# MKVCO.net
KiCad netlist of a schematic drawn in EAGLE
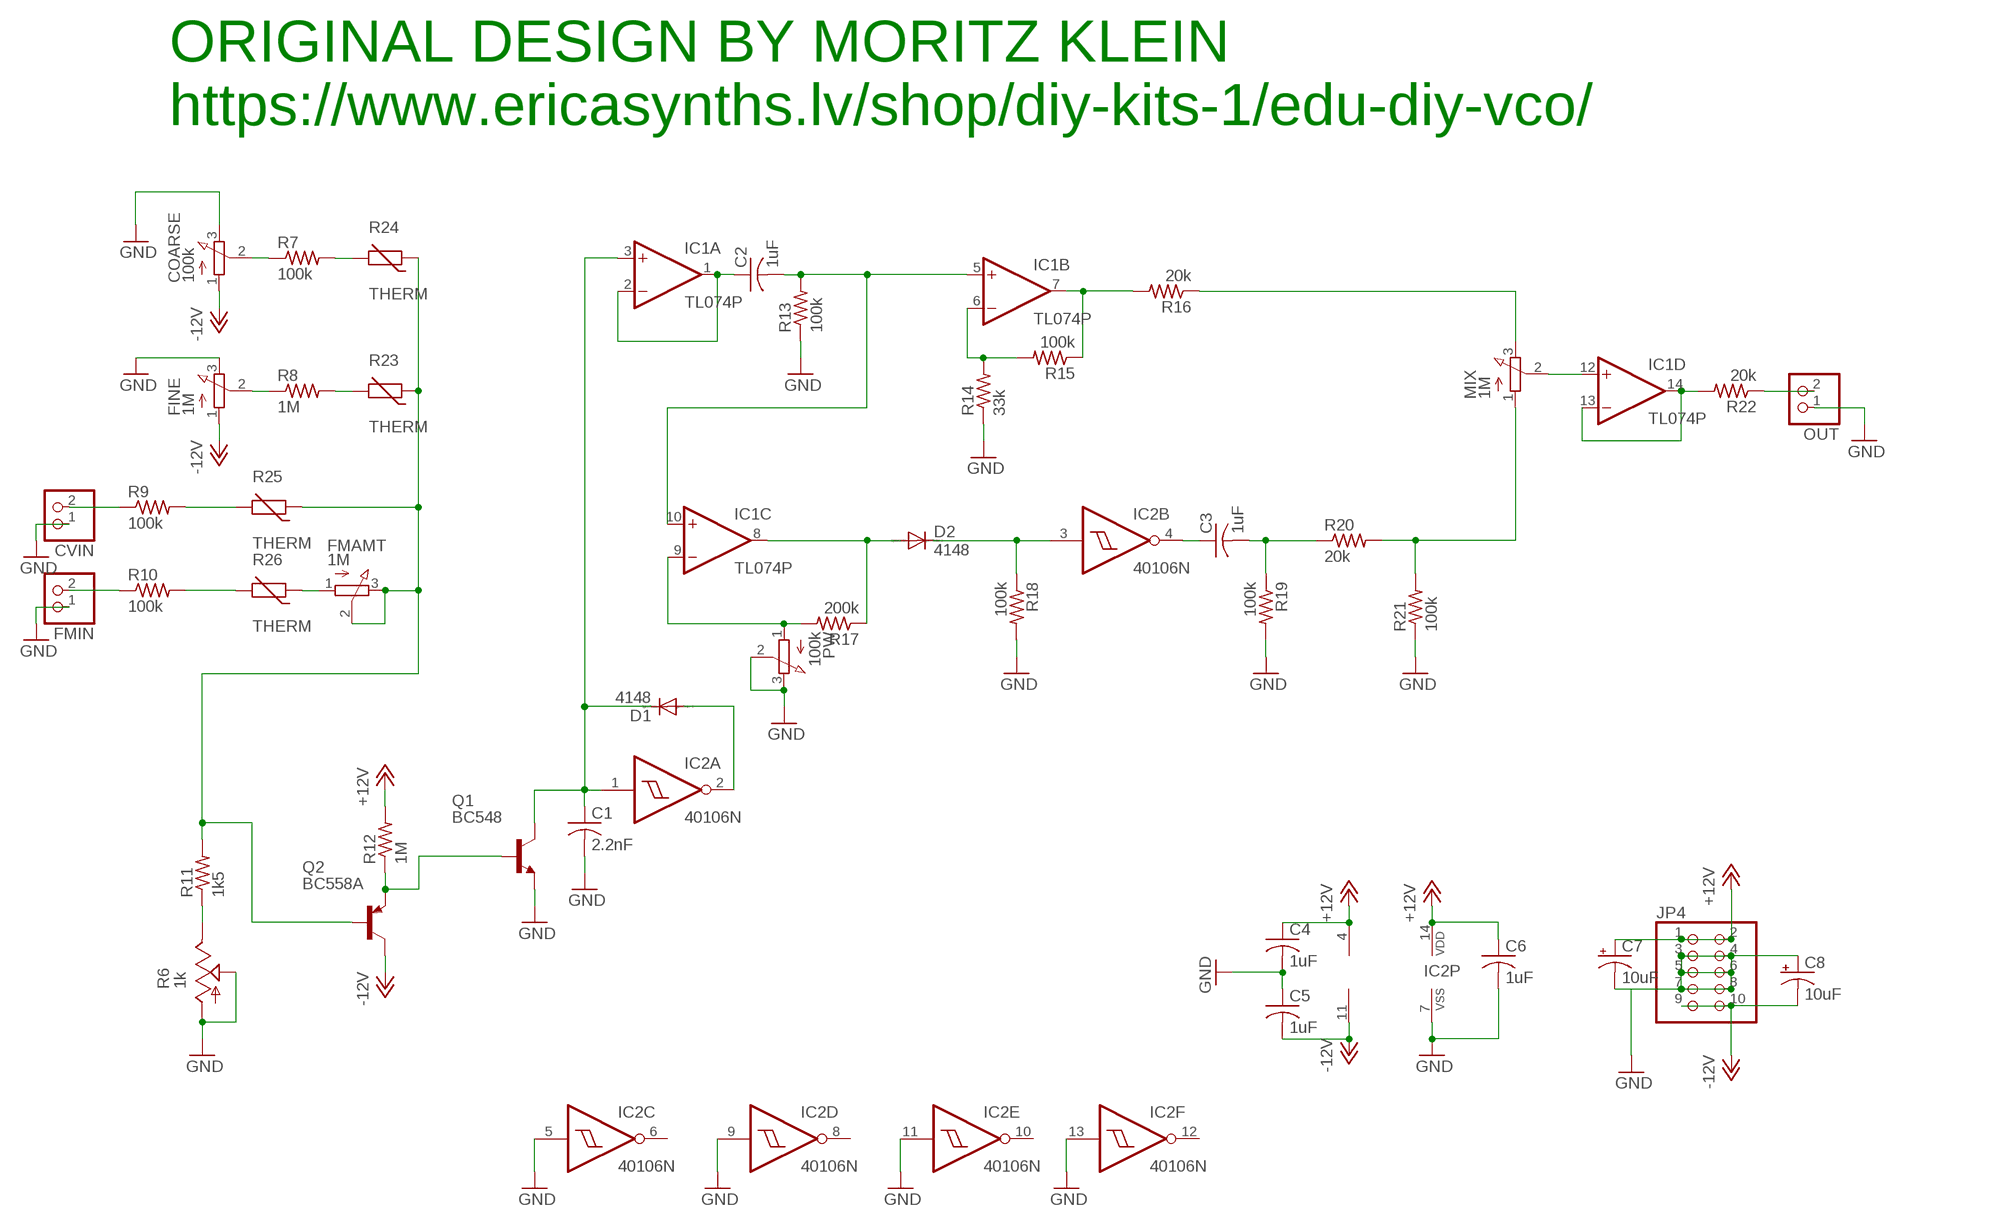
[diagram p0: schematic, sheet 1]

(export (version "E")
  (design (tool "Eeschema 10.0.6"))
  (components
    (comp (ref "C1")
      (value "2.2nF")
      (footprint "eagle-import:C050-025X075")
      (libsource (lib "eagle-import") (part "C-US050-025X075"))
    )
    (comp (ref "C2")
      (value "1uF")
      (footprint "eagle-import:C050-025X075")
      (libsource (lib "eagle-import") (part "C-US050-025X075"))
    )
    (comp (ref "C3")
      (value "1uF")
      (footprint "eagle-import:C050-025X075")
      (libsource (lib "eagle-import") (part "C-US050-025X075"))
    )
    (comp (ref "C4")
      (value "1uF")
      (footprint "eagle-import:C050-024X044")
      (libsource (lib "eagle-import") (part "C-US050-024X044"))
    )
    (comp (ref "C5")
      (value "1uF")
      (footprint "eagle-import:C050-024X044")
      (libsource (lib "eagle-import") (part "C-US050-024X044"))
    )
    (comp (ref "C6")
      (value "1uF")
      (footprint "eagle-import:C050-024X044")
      (libsource (lib "eagle-import") (part "C-US050-024X044"))
    )
    (comp (ref "C7")
      (value "10uF")
      (footprint "eagle-import:E1,8-4")
      (libsource (lib "eagle-import") (part "CPOL-USE1.8-4"))
    )
    (comp (ref "C8")
      (value "10uF")
      (footprint "eagle-import:E1,8-4")
      (libsource (lib "eagle-import") (part "CPOL-USE1.8-4"))
    )
    (comp (ref "COARSE")
      (value "100k")
      (footprint "eagle-import:3RP_1610N")
      (libsource (lib "eagle-import") (part "3RP/1610N"))
    )
    (comp (ref "CVIN")
      (value "PINHD-1X2")
      (footprint "eagle-import:1X02")
      (libsource (lib "eagle-import") (part "PINHD-1X2"))
    )
    (comp (ref "D1")
      (value "4148")
      (footprint "eagle-import:DO35-7")
      (libsource (lib "eagle-import") (part "1N4148DO35-7"))
    )
    (comp (ref "D2")
      (value "4148")
      (footprint "eagle-import:DO35-7")
      (libsource (lib "eagle-import") (part "1N4148DO35-7"))
    )
    (comp (ref "FINE")
      (value "1M")
      (footprint "eagle-import:3RP_1610N")
      (libsource (lib "eagle-import") (part "3RP/1610N"))
    )
    (comp (ref "FMAMT")
      (value "1M")
      (footprint "eagle-import:3RP_1610N")
      (libsource (lib "eagle-import") (part "3RP/1610N"))
    )
    (comp (ref "FMIN")
      (value "PINHD-1X2")
      (footprint "eagle-import:1X02")
      (libsource (lib "eagle-import") (part "PINHD-1X2"))
    )
    (comp (ref "IC1")
      (value "TL074P")
      (footprint "eagle-import:DIL14")
      (libsource (lib "eagle-import") (part "TL074P"))
    )
    (comp (ref "IC2")
      (value "40106N")
      (footprint "eagle-import:DIL14")
      (libsource (lib "eagle-import") (part "40106N"))
    )
    (comp (ref "JP4")
      (value "PINHD-2X5")
      (footprint "eagle-import:2X05")
      (libsource (lib "eagle-import") (part "PINHD-2X5"))
    )
    (comp (ref "MIX")
      (value "1M")
      (footprint "eagle-import:3RP_1610N")
      (libsource (lib "eagle-import") (part "3RP/1610N"))
    )
    (comp (ref "OUT")
      (value "PINHD-1X2")
      (footprint "eagle-import:1X02")
      (libsource (lib "eagle-import") (part "PINHD-1X2"))
    )
    (comp (ref "PW")
      (value "100k")
      (footprint "eagle-import:3RP_1610N")
      (libsource (lib "eagle-import") (part "3RP/1610N"))
    )
    (comp (ref "Q1")
      (value "BC548")
      (footprint "eagle-import:TO92-EBC")
      (libsource (lib "eagle-import") (part "BC548"))
    )
    (comp (ref "Q2")
      (value "BC558A")
      (footprint "eagle-import:TO92-EBC")
      (libsource (lib "eagle-import") (part "BC558A"))
    )
    (comp (ref "R6")
      (value "1k")
      (footprint "eagle-import:B64Y")
      (libsource (lib "eagle-import") (part "TRIM_US-B64Y"))
    )
    (comp (ref "R7")
      (value "100k")
      (footprint "eagle-import:0207_10")
      (libsource (lib "eagle-import") (part "R-US_0207/10"))
    )
    (comp (ref "R8")
      (value "1M")
      (footprint "eagle-import:0207_10")
      (libsource (lib "eagle-import") (part "R-US_0207/10"))
    )
    (comp (ref "R9")
      (value "100k")
      (footprint "eagle-import:0207_10")
      (libsource (lib "eagle-import") (part "R-US_0207/10"))
    )
    (comp (ref "R10")
      (value "100k")
      (footprint "eagle-import:0207_10")
      (libsource (lib "eagle-import") (part "R-US_0207/10"))
    )
    (comp (ref "R11")
      (value "1k5")
      (footprint "eagle-import:0207_10")
      (libsource (lib "eagle-import") (part "R-US_0207/10"))
    )
    (comp (ref "R12")
      (value "1M")
      (footprint "eagle-import:0207_10")
      (libsource (lib "eagle-import") (part "R-US_0207/10"))
    )
    (comp (ref "R13")
      (value "100k")
      (footprint "eagle-import:0207_10")
      (libsource (lib "eagle-import") (part "R-US_0207/10"))
    )
    (comp (ref "R14")
      (value "33k")
      (footprint "eagle-import:0207_10")
      (libsource (lib "eagle-import") (part "R-US_0207/10"))
    )
    (comp (ref "R15")
      (value "100k")
      (footprint "eagle-import:0207_10")
      (libsource (lib "eagle-import") (part "R-US_0207/10"))
    )
    (comp (ref "R16")
      (value "20k")
      (footprint "eagle-import:0207_10")
      (libsource (lib "eagle-import") (part "R-US_0207/10"))
    )
    (comp (ref "R17")
      (value "200k")
      (footprint "eagle-import:0207_10")
      (libsource (lib "eagle-import") (part "R-US_0207/10"))
    )
    (comp (ref "R18")
      (value "100k")
      (footprint "eagle-import:0207_10")
      (libsource (lib "eagle-import") (part "R-US_0207/10"))
    )
    (comp (ref "R19")
      (value "100k")
      (footprint "eagle-import:0207_10")
      (libsource (lib "eagle-import") (part "R-US_0207/10"))
    )
    (comp (ref "R20")
      (value "20k")
      (footprint "eagle-import:0207_10")
      (libsource (lib "eagle-import") (part "R-US_0207/10"))
    )
    (comp (ref "R21")
      (value "100k")
      (footprint "eagle-import:0207_10")
      (libsource (lib "eagle-import") (part "R-US_0207/10"))
    )
    (comp (ref "R22")
      (value "20k")
      (footprint "eagle-import:0207_10")
      (libsource (lib "eagle-import") (part "R-US_0207/10"))
    )
    (comp (ref "R23")
      (value "THERM")
      (footprint "eagle-import:RS-2,5")
      (libsource (lib "eagle-import") (part "THERMISTOR-2,5"))
    )
    (comp (ref "R24")
      (value "THERM")
      (footprint "eagle-import:RS-2,5")
      (libsource (lib "eagle-import") (part "THERMISTOR-2,5"))
    )
    (comp (ref "R25")
      (value "THERM")
      (footprint "eagle-import:RS-2,5")
      (libsource (lib "eagle-import") (part "THERMISTOR-2,5"))
    )
    (comp (ref "R26")
      (value "THERM")
      (footprint "eagle-import:RS-2,5")
      (libsource (lib "eagle-import") (part "THERMISTOR-2,5"))
    )
  )
  (nets
    (net (code "1") (name "+12V") (class "Default")
      (node (ref "C4") (pin "1") (pinfunction "1_1") (pintype "passive"))
      (node (ref "C6") (pin "1") (pinfunction "1_1") (pintype "passive"))
      (node (ref "C7") (pin "+") (pinfunction "+_+") (pintype "passive"))
      (node (ref "IC1") (pin "4") (pinfunction "V+_4") (pintype "power_in"))
      (node (ref "IC2") (pin "14") (pinfunction "VDD_14") (pintype "power_in"))
      (node (ref "JP4") (pin "1") (pinfunction "1_1") (pintype "passive"))
      (node (ref "JP4") (pin "2") (pinfunction "2_2") (pintype "passive"))
      (node (ref "R12") (pin "2") (pinfunction "2_2") (pintype "passive"))
    )
    (net (code "2") (name "-12V") (class "Default")
      (node (ref "C5") (pin "2") (pinfunction "2_2") (pintype "passive"))
      (node (ref "C8") (pin "-") (pinfunction "-_-") (pintype "passive"))
      (node (ref "COARSE") (pin "1") (pinfunction "A_1") (pintype "passive"))
      (node (ref "FINE") (pin "1") (pinfunction "A_1") (pintype "passive"))
      (node (ref "IC1") (pin "11") (pinfunction "V-_11") (pintype "power_in"))
      (node (ref "JP4") (pin "10") (pinfunction "10_10") (pintype "passive"))
      (node (ref "JP4") (pin "9") (pinfunction "9_9") (pintype "passive"))
      (node (ref "Q2") (pin "C") (pinfunction "C_C") (pintype "passive"))
    )
    (net (code "3") (name "GND") (class "Default")
      (node (ref "C1") (pin "2") (pinfunction "2_2") (pintype "passive"))
      (node (ref "C4") (pin "2") (pinfunction "2_2") (pintype "passive"))
      (node (ref "C5") (pin "1") (pinfunction "1_1") (pintype "passive"))
      (node (ref "C6") (pin "2") (pinfunction "2_2") (pintype "passive"))
      (node (ref "C7") (pin "-") (pinfunction "-_-") (pintype "passive"))
      (node (ref "C8") (pin "+") (pinfunction "+_+") (pintype "passive"))
      (node (ref "COARSE") (pin "3") (pinfunction "E_3") (pintype "passive"))
      (node (ref "CVIN") (pin "1") (pinfunction "1_1") (pintype "passive"))
      (node (ref "FINE") (pin "3") (pinfunction "E_3") (pintype "passive"))
      (node (ref "FMIN") (pin "1") (pinfunction "1_1") (pintype "passive"))
      (node (ref "IC2") (pin "11") (pinfunction "I_11") (pintype "input"))
      (node (ref "IC2") (pin "13") (pinfunction "I_13") (pintype "input"))
      (node (ref "IC2") (pin "5") (pinfunction "I_5") (pintype "input"))
      (node (ref "IC2") (pin "7") (pinfunction "VSS_7") (pintype "power_in"))
      (node (ref "IC2") (pin "9") (pinfunction "I_9") (pintype "input"))
      (node (ref "JP4") (pin "3") (pinfunction "3_3") (pintype "passive"))
      (node (ref "JP4") (pin "4") (pinfunction "4_4") (pintype "passive"))
      (node (ref "JP4") (pin "5") (pinfunction "5_5") (pintype "passive"))
      (node (ref "JP4") (pin "6") (pinfunction "6_6") (pintype "passive"))
      (node (ref "JP4") (pin "7") (pinfunction "7_7") (pintype "passive"))
      (node (ref "JP4") (pin "8") (pinfunction "8_8") (pintype "passive"))
      (node (ref "OUT") (pin "1") (pinfunction "1_1") (pintype "passive"))
      (node (ref "PW") (pin "2") (pinfunction "S_2") (pintype "passive"))
      (node (ref "PW") (pin "3") (pinfunction "E_3") (pintype "passive"))
      (node (ref "Q1") (pin "E") (pinfunction "E_E") (pintype "passive"))
      (node (ref "R13") (pin "1") (pinfunction "1_1") (pintype "passive"))
      (node (ref "R14") (pin "1") (pinfunction "1_1") (pintype "passive"))
      (node (ref "R18") (pin "2") (pinfunction "2_2") (pintype "passive"))
      (node (ref "R19") (pin "2") (pinfunction "2_2") (pintype "passive"))
      (node (ref "R21") (pin "1") (pinfunction "1_1") (pintype "passive"))
      (node (ref "R6") (pin "A") (pinfunction "A_A") (pintype "passive"))
      (node (ref "R6") (pin "S") (pinfunction "S_S") (pintype "passive"))
    )
    (net (code "4") (name "Net-(C3-Pad2)") (class "Default")
      (node (ref "C3") (pin "2") (pinfunction "2_2") (pintype "passive"))
      (node (ref "R19") (pin "1") (pinfunction "1_1") (pintype "passive"))
      (node (ref "R20") (pin "1") (pinfunction "1_1") (pintype "passive"))
    )
    (net (code "5") (name "Net-(COARSE-S)") (class "Default")
      (node (ref "COARSE") (pin "2") (pinfunction "S_2") (pintype "passive"))
      (node (ref "R7") (pin "1") (pinfunction "1_1") (pintype "passive"))
    )
    (net (code "6") (name "Net-(CVIN-Pad2)") (class "Default")
      (node (ref "CVIN") (pin "2") (pinfunction "2_2") (pintype "passive"))
      (node (ref "R9") (pin "1") (pinfunction "1_1") (pintype "passive"))
    )
    (net (code "7") (name "Net-(FINE-S)") (class "Default")
      (node (ref "FINE") (pin "2") (pinfunction "S_2") (pintype "passive"))
      (node (ref "R8") (pin "1") (pinfunction "1_1") (pintype "passive"))
    )
    (net (code "8") (name "Net-(FMAMT-A)") (class "Default")
      (node (ref "FMAMT") (pin "1") (pinfunction "A_1") (pintype "passive"))
      (node (ref "R26") (pin "1") (pinfunction "1_1") (pintype "passive"))
    )
    (net (code "9") (name "Net-(FMAMT-E)") (class "Default")
      (node (ref "FMAMT") (pin "2") (pinfunction "S_2") (pintype "passive"))
      (node (ref "FMAMT") (pin "3") (pinfunction "E_3") (pintype "passive"))
      (node (ref "Q2") (pin "B") (pinfunction "B_B") (pintype "passive"))
      (node (ref "R11") (pin "2") (pinfunction "2_2") (pintype "passive"))
      (node (ref "R23") (pin "1") (pinfunction "1_1") (pintype "passive"))
      (node (ref "R24") (pin "1") (pinfunction "1_1") (pintype "passive"))
      (node (ref "R25") (pin "1") (pinfunction "1_1") (pintype "passive"))
    )
    (net (code "10") (name "Net-(FMIN-Pad2)") (class "Default")
      (node (ref "FMIN") (pin "2") (pinfunction "2_2") (pintype "passive"))
      (node (ref "R10") (pin "1") (pinfunction "1_1") (pintype "passive"))
    )
    (net (code "11") (name "Net-(IC1A-+IN)") (class "Default")
      (node (ref "C1") (pin "1") (pinfunction "1_1") (pintype "passive"))
      (node (ref "D1") (pin "C") (pinfunction "C_C") (pintype "passive"))
      (node (ref "IC1") (pin "3") (pinfunction "+IN_3") (pintype "input"))
      (node (ref "IC2") (pin "1") (pinfunction "I_1") (pintype "input"))
      (node (ref "Q1") (pin "C") (pinfunction "C_C") (pintype "passive"))
    )
    (net (code "12") (name "Net-(IC1A--IN)") (class "Default")
      (node (ref "C2") (pin "1") (pinfunction "1_1") (pintype "passive"))
      (node (ref "IC1") (pin "1") (pinfunction "OUT_1") (pintype "output"))
      (node (ref "IC1") (pin "2") (pinfunction "-IN_2") (pintype "input"))
    )
    (net (code "13") (name "Net-(IC1B-+IN)") (class "Default")
      (node (ref "C2") (pin "2") (pinfunction "2_2") (pintype "passive"))
      (node (ref "IC1") (pin "10") (pinfunction "+IN_10") (pintype "input"))
      (node (ref "IC1") (pin "5") (pinfunction "+IN_5") (pintype "input"))
      (node (ref "R13") (pin "2") (pinfunction "2_2") (pintype "passive"))
    )
    (net (code "14") (name "Net-(IC1B--IN)") (class "Default")
      (node (ref "IC1") (pin "6") (pinfunction "-IN_6") (pintype "input"))
      (node (ref "R14") (pin "2") (pinfunction "2_2") (pintype "passive"))
      (node (ref "R15") (pin "2") (pinfunction "2_2") (pintype "passive"))
    )
    (net (code "15") (name "Net-(IC1B-OUT)") (class "Default")
      (node (ref "IC1") (pin "7") (pinfunction "OUT_7") (pintype "output"))
      (node (ref "R15") (pin "1") (pinfunction "1_1") (pintype "passive"))
      (node (ref "R16") (pin "2") (pinfunction "2_2") (pintype "passive"))
    )
    (net (code "16") (name "Net-(IC1C--IN)") (class "Default")
      (node (ref "IC1") (pin "9") (pinfunction "-IN_9") (pintype "input"))
      (node (ref "PW") (pin "1") (pinfunction "A_1") (pintype "passive"))
      (node (ref "R17") (pin "2") (pinfunction "2_2") (pintype "passive"))
    )
    (net (code "17") (name "Net-(IC1C-OUT)") (class "Default")
      (node (ref "D2") (pin "A") (pinfunction "A_A") (pintype "passive"))
      (node (ref "IC1") (pin "8") (pinfunction "OUT_8") (pintype "output"))
      (node (ref "R17") (pin "1") (pinfunction "1_1") (pintype "passive"))
    )
    (net (code "18") (name "Net-(IC1D-+IN)") (class "Default")
      (node (ref "IC1") (pin "12") (pinfunction "+IN_12") (pintype "input"))
      (node (ref "MIX") (pin "2") (pinfunction "S_2") (pintype "passive"))
    )
    (net (code "19") (name "Net-(IC1D--IN)") (class "Default")
      (node (ref "IC1") (pin "13") (pinfunction "-IN_13") (pintype "input"))
      (node (ref "IC1") (pin "14") (pinfunction "OUT_14") (pintype "output"))
      (node (ref "R22") (pin "2") (pinfunction "2_2") (pintype "passive"))
    )
    (net (code "20") (name "Net-(IC2A-O)") (class "Default")
      (node (ref "D1") (pin "A") (pinfunction "A_A") (pintype "passive"))
      (node (ref "IC2") (pin "2") (pinfunction "O_2") (pintype "output"))
    )
    (net (code "21") (name "Net-(IC2B-I)") (class "Default")
      (node (ref "D2") (pin "C") (pinfunction "C_C") (pintype "passive"))
      (node (ref "IC2") (pin "3") (pinfunction "I_3") (pintype "input"))
      (node (ref "R18") (pin "1") (pinfunction "1_1") (pintype "passive"))
    )
    (net (code "22") (name "Net-(IC2B-O)") (class "Default")
      (node (ref "C3") (pin "1") (pinfunction "1_1") (pintype "passive"))
      (node (ref "IC2") (pin "4") (pinfunction "O_4") (pintype "output"))
    )
    (net (code "23") (name "Net-(MIX-A)") (class "Default")
      (node (ref "MIX") (pin "1") (pinfunction "A_1") (pintype "passive"))
      (node (ref "R20") (pin "2") (pinfunction "2_2") (pintype "passive"))
      (node (ref "R21") (pin "2") (pinfunction "2_2") (pintype "passive"))
    )
    (net (code "24") (name "Net-(MIX-E)") (class "Default")
      (node (ref "MIX") (pin "3") (pinfunction "E_3") (pintype "passive"))
      (node (ref "R16") (pin "1") (pinfunction "1_1") (pintype "passive"))
    )
    (net (code "25") (name "Net-(OUT-Pad2)") (class "Default")
      (node (ref "OUT") (pin "2") (pinfunction "2_2") (pintype "passive"))
      (node (ref "R22") (pin "1") (pinfunction "1_1") (pintype "passive"))
    )
    (net (code "26") (name "Net-(Q1-PadB)") (class "Default")
      (node (ref "Q1") (pin "B") (pinfunction "B_B") (pintype "passive"))
      (node (ref "Q2") (pin "E") (pinfunction "E_E") (pintype "passive"))
      (node (ref "R12") (pin "1") (pinfunction "1_1") (pintype "passive"))
    )
    (net (code "27") (name "Net-(R10-Pad2)") (class "Default")
      (node (ref "R10") (pin "2") (pinfunction "2_2") (pintype "passive"))
      (node (ref "R26") (pin "2") (pinfunction "2_2") (pintype "passive"))
    )
    (net (code "28") (name "Net-(R11-Pad1)") (class "Default")
      (node (ref "R11") (pin "1") (pinfunction "1_1") (pintype "passive"))
      (node (ref "R6") (pin "E") (pinfunction "E_E") (pintype "passive"))
    )
    (net (code "29") (name "Net-(R23-Pad2)") (class "Default")
      (node (ref "R23") (pin "2") (pinfunction "2_2") (pintype "passive"))
      (node (ref "R8") (pin "2") (pinfunction "2_2") (pintype "passive"))
    )
    (net (code "30") (name "Net-(R24-Pad2)") (class "Default")
      (node (ref "R24") (pin "2") (pinfunction "2_2") (pintype "passive"))
      (node (ref "R7") (pin "2") (pinfunction "2_2") (pintype "passive"))
    )
    (net (code "31") (name "Net-(R25-Pad2)") (class "Default")
      (node (ref "R25") (pin "2") (pinfunction "2_2") (pintype "passive"))
      (node (ref "R9") (pin "2") (pinfunction "2_2") (pintype "passive"))
    )
    (net (code "32") (name "unconnected-(IC2C-O-Pad6)") (class "Default")
      (node (ref "IC2") (pin "6") (pinfunction "O_6") (pintype "output"))
    )
    (net (code "33") (name "unconnected-(IC2D-O-Pad8)") (class "Default")
      (node (ref "IC2") (pin "8") (pinfunction "O_8") (pintype "output"))
    )
    (net (code "34") (name "unconnected-(IC2E-O-Pad10)") (class "Default")
      (node (ref "IC2") (pin "10") (pinfunction "O_10") (pintype "output"))
    )
    (net (code "35") (name "unconnected-(IC2F-O-Pad12)") (class "Default")
      (node (ref "IC2") (pin "12") (pinfunction "O_12") (pintype "output"))
    )
  )
)
